# TamagotchiMainBoard.net
KiCad netlist of a schematic drawn in Altium Designer
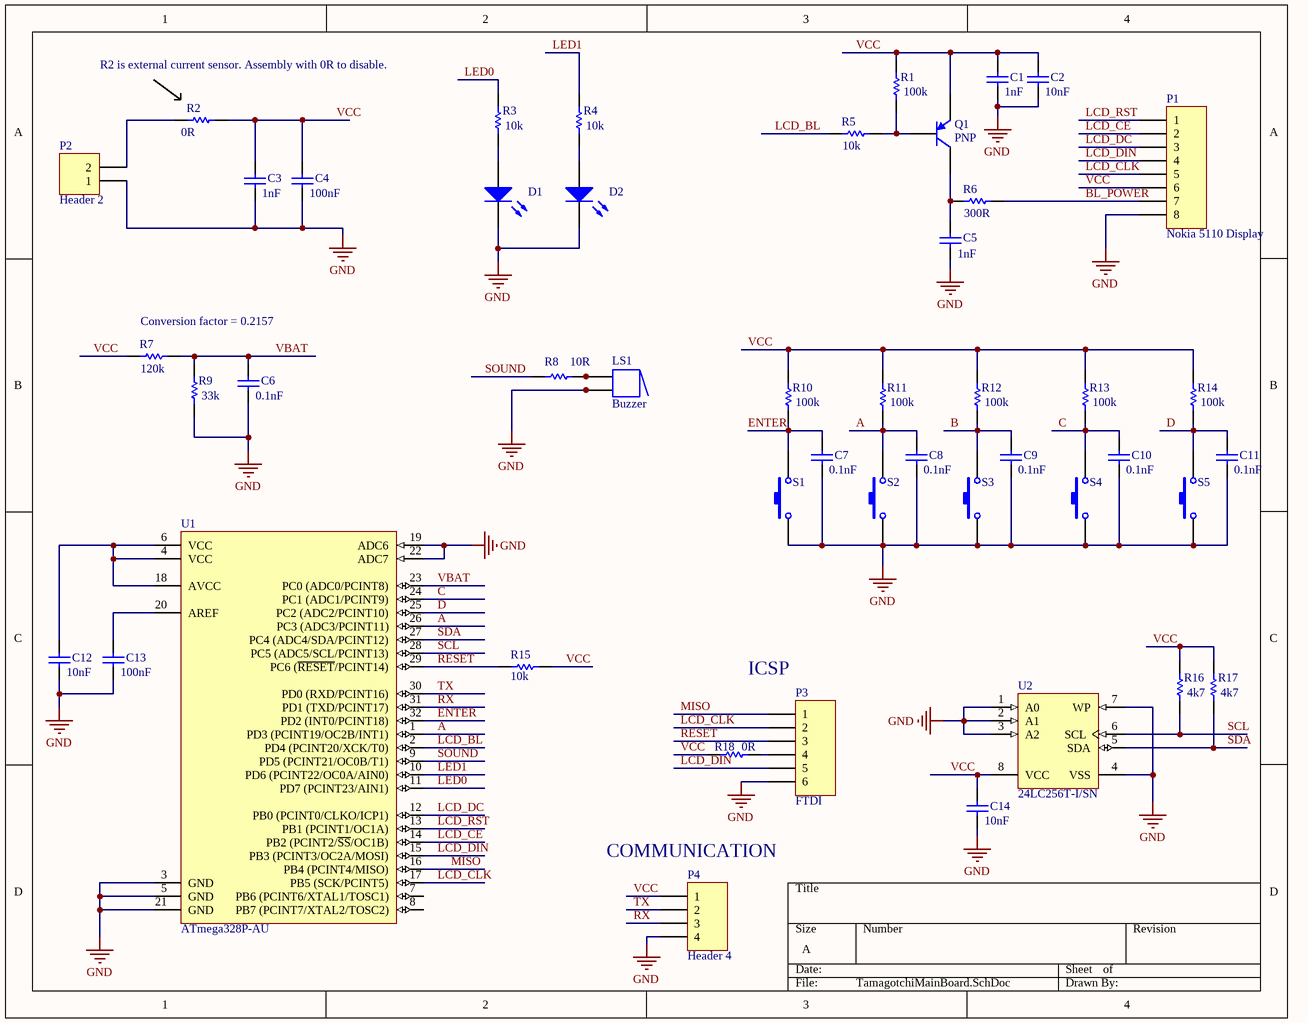
[diagram p0: TamagotchiMainBoard.SchDoc]

(export (version "E")
  (design (tool "Eeschema 10.0.6"))
  (components
    (comp (ref "C1")
      (value "1nF")
      (footprint "Miscellaneous Devices:C0805")
      (description "Capacitor")
      (fields (field (name "Comment") "Cap") (field (name "PUBLISHER") "Altium Limited"))
      (libsource (lib "Miscellaneous Devices") (part "Cap"))
    )
    (comp (ref "C2")
      (value "10nF")
      (footprint "Miscellaneous Devices:C0805")
      (description "Capacitor")
      (fields (field (name "Comment") "Cap") (field (name "PUBLISHER") "Altium Limited"))
      (libsource (lib "Miscellaneous Devices") (part "Cap"))
    )
    (comp (ref "C3")
      (value "1nF")
      (footprint "Miscellaneous Devices:C0805")
      (description "Capacitor")
      (fields (field (name "Comment") "Cap") (field (name "PUBLISHER") "Altium Limited"))
      (libsource (lib "Miscellaneous Devices") (part "Cap"))
    )
    (comp (ref "C4")
      (value "100nF")
      (footprint "Miscellaneous Devices:C0805")
      (description "Capacitor")
      (fields (field (name "Comment") "Cap") (field (name "PUBLISHER") "Altium Limited"))
      (libsource (lib "Miscellaneous Devices") (part "Cap"))
    )
    (comp (ref "C5")
      (value "1nF")
      (footprint "Miscellaneous Devices:C0805")
      (description "Capacitor")
      (fields (field (name "Comment") "Cap") (field (name "PUBLISHER") "Altium Limited"))
      (libsource (lib "Miscellaneous Devices") (part "Cap"))
    )
    (comp (ref "C6")
      (value "0.1nF")
      (footprint "Miscellaneous Devices:C0805")
      (description "Capacitor")
      (fields (field (name "Comment") "Cap") (field (name "PUBLISHER") "Altium Limited"))
      (libsource (lib "Miscellaneous Devices") (part "Cap"))
    )
    (comp (ref "C7")
      (value "0.1nF")
      (footprint "Miscellaneous Devices:C0805")
      (description "Capacitor")
      (fields (field (name "Comment") "Cap") (field (name "PUBLISHER") "Altium Limited"))
      (libsource (lib "Miscellaneous Devices") (part "Cap"))
    )
    (comp (ref "C8")
      (value "0.1nF")
      (footprint "Miscellaneous Devices:C0805")
      (description "Capacitor")
      (fields (field (name "Comment") "Cap") (field (name "PUBLISHER") "Altium Limited"))
      (libsource (lib "Miscellaneous Devices") (part "Cap"))
    )
    (comp (ref "C9")
      (value "0.1nF")
      (footprint "Miscellaneous Devices:C0805")
      (description "Capacitor")
      (fields (field (name "Comment") "Cap") (field (name "PUBLISHER") "Altium Limited"))
      (libsource (lib "Miscellaneous Devices") (part "Cap"))
    )
    (comp (ref "C10")
      (value "0.1nF")
      (footprint "Miscellaneous Devices:C0805")
      (description "Capacitor")
      (fields (field (name "Comment") "Cap") (field (name "PUBLISHER") "Altium Limited"))
      (libsource (lib "Miscellaneous Devices") (part "Cap"))
    )
    (comp (ref "C11")
      (value "0.1nF")
      (footprint "Miscellaneous Devices:C0805")
      (description "Capacitor")
      (fields (field (name "Comment") "Cap") (field (name "PUBLISHER") "Altium Limited"))
      (libsource (lib "Miscellaneous Devices") (part "Cap"))
    )
    (comp (ref "C12")
      (value "10nF")
      (footprint "Miscellaneous Devices:C0805")
      (description "Capacitor")
      (fields (field (name "Comment") "Cap") (field (name "PUBLISHER") "Altium Limited"))
      (libsource (lib "Miscellaneous Devices") (part "Cap"))
    )
    (comp (ref "C13")
      (value "100nF")
      (footprint "Miscellaneous Devices:C0805")
      (description "Capacitor")
      (fields (field (name "Comment") "Cap") (field (name "PUBLISHER") "Altium Limited"))
      (libsource (lib "Miscellaneous Devices") (part "Cap"))
    )
    (comp (ref "C14")
      (value "10nF")
      (footprint "Miscellaneous Devices:C0805")
      (description "Capacitor")
      (fields (field (name "Comment") "Cap") (field (name "PUBLISHER") "Altium Limited"))
      (libsource (lib "Miscellaneous Devices") (part "Cap"))
    )
    (comp (ref "D1")
      (value "LED0")
      (description "Typical INFRARED GaAs LED")
      (fields (field (name "PUBLISHER") "Altium Limited"))
      (libsource (lib "Miscellaneous Devices") (part "LED0"))
    )
    (comp (ref "D2")
      (value "LED0")
      (description "Typical INFRARED GaAs LED")
      (fields (field (name "PUBLISHER") "Altium Limited"))
      (libsource (lib "Miscellaneous Devices") (part "LED0"))
    )
    (comp (ref "LS1")
      (value "Buzzer")
      (footprint "ABSM-1574")
      (description "Magnetic Transducer Buzzer")
      (fields (field (name "PUBLISHER") "Altium Limited"))
      (libsource (lib "Miscellaneous Devices") (part "Buzzer"))
    )
    (comp (ref "P1")
      (value "Nokia 5110 Display")
      (footprint "HDR1X8")
      (description "Header, 8-Pin")
      (fields (field (name "PUBLISHER") "Altium Limited"))
      (libsource (lib "Miscellaneous Connectors") (part "Header 8"))
    )
    (comp (ref "P2")
      (value "Header 2")
      (footprint "HDR1X2")
      (description "Header, 2-Pin")
      (fields (field (name "PUBLISHER") "Altium Limited"))
      (libsource (lib "Miscellaneous Connectors") (part "Header 2"))
    )
    (comp (ref "P3")
      (value "FTDI")
      (footprint "HDR1X6")
      (description "Header, 6-Pin")
      (fields (field (name "PUBLISHER") "Altium Limited"))
      (libsource (lib "Miscellaneous Connectors") (part "Header 6"))
    )
    (comp (ref "P4")
      (value "Header 4")
      (footprint "HDR1X4")
      (description "Header, 4-Pin")
      (fields (field (name "PUBLISHER") "Altium Limited"))
      (libsource (lib "Miscellaneous Connectors") (part "Header 4"))
    )
    (comp (ref "Q1")
      (value "PNP")
      (footprint "SOT-23B_N")
      (description "PNP Bipolar Transistor")
      (fields (field (name "PUBLISHER") "Altium Limited"))
      (libsource (lib "Miscellaneous Devices") (part "PNP"))
    )
    (comp (ref "R1")
      (value "100k")
      (footprint "6-0805_M")
      (description "Resistor")
      (fields (field (name "Comment") "Res1") (field (name "PUBLISHER") "Altium Limited"))
      (libsource (lib "Miscellaneous Devices") (part "Res1"))
    )
    (comp (ref "R2")
      (value "0R")
      (footprint "6-0805_M")
      (description "Resistor")
      (fields (field (name "Comment") "Res1") (field (name "PUBLISHER") "Altium Limited"))
      (libsource (lib "Miscellaneous Devices") (part "Res1"))
    )
    (comp (ref "R3")
      (value "10k")
      (footprint "6-0805_M")
      (description "Resistor")
      (fields (field (name "Comment") "Res1") (field (name "PUBLISHER") "Altium Limited"))
      (libsource (lib "Miscellaneous Devices") (part "Res1"))
    )
    (comp (ref "R4")
      (value "10k")
      (footprint "6-0805_M")
      (description "Resistor")
      (fields (field (name "Comment") "Res1") (field (name "PUBLISHER") "Altium Limited"))
      (libsource (lib "Miscellaneous Devices") (part "Res1"))
    )
    (comp (ref "R5")
      (value "10k")
      (footprint "6-0805_M")
      (description "Resistor")
      (fields (field (name "Comment") "Res1") (field (name "PUBLISHER") "Altium Limited"))
      (libsource (lib "Miscellaneous Devices") (part "Res1"))
    )
    (comp (ref "R6")
      (value "300R")
      (footprint "6-0805_M")
      (description "Resistor")
      (fields (field (name "Comment") "Res1") (field (name "PUBLISHER") "Altium Limited"))
      (libsource (lib "Miscellaneous Devices") (part "Res1"))
    )
    (comp (ref "R7")
      (value "120k")
      (footprint "6-0805_M")
      (description "Resistor")
      (fields (field (name "Comment") "Res1") (field (name "PUBLISHER") "Altium Limited"))
      (libsource (lib "Miscellaneous Devices") (part "Res1"))
    )
    (comp (ref "R8")
      (value "10R")
      (footprint "6-0805_M")
      (description "Resistor")
      (fields (field (name "Comment") "Res1") (field (name "PUBLISHER") "Altium Limited"))
      (libsource (lib "Miscellaneous Devices") (part "Res1"))
    )
    (comp (ref "R9")
      (value "33k")
      (footprint "6-0805_M")
      (description "Resistor")
      (fields (field (name "Comment") "Res1") (field (name "PUBLISHER") "Altium Limited"))
      (libsource (lib "Miscellaneous Devices") (part "Res1"))
    )
    (comp (ref "R10")
      (value "100k")
      (footprint "6-0805_M")
      (description "Resistor")
      (fields (field (name "Comment") "Res1") (field (name "PUBLISHER") "Altium Limited"))
      (libsource (lib "Miscellaneous Devices") (part "Res1"))
    )
    (comp (ref "R11")
      (value "100k")
      (footprint "6-0805_M")
      (description "Resistor")
      (fields (field (name "Comment") "Res1") (field (name "PUBLISHER") "Altium Limited"))
      (libsource (lib "Miscellaneous Devices") (part "Res1"))
    )
    (comp (ref "R12")
      (value "100k")
      (footprint "6-0805_M")
      (description "Resistor")
      (fields (field (name "Comment") "Res1") (field (name "PUBLISHER") "Altium Limited"))
      (libsource (lib "Miscellaneous Devices") (part "Res1"))
    )
    (comp (ref "R13")
      (value "100k")
      (footprint "6-0805_M")
      (description "Resistor")
      (fields (field (name "Comment") "Res1") (field (name "PUBLISHER") "Altium Limited"))
      (libsource (lib "Miscellaneous Devices") (part "Res1"))
    )
    (comp (ref "R14")
      (value "100k")
      (footprint "6-0805_M")
      (description "Resistor")
      (fields (field (name "Comment") "Res1") (field (name "PUBLISHER") "Altium Limited"))
      (libsource (lib "Miscellaneous Devices") (part "Res1"))
    )
    (comp (ref "R15")
      (value "10k")
      (footprint "6-0805_M")
      (description "Resistor")
      (fields (field (name "Comment") "Res1") (field (name "PUBLISHER") "Altium Limited"))
      (libsource (lib "Miscellaneous Devices") (part "Res1"))
    )
    (comp (ref "R16")
      (value "4k7")
      (footprint "6-0805_M")
      (description "Resistor")
      (fields (field (name "Comment") "Res1") (field (name "PUBLISHER") "Altium Limited"))
      (libsource (lib "Miscellaneous Devices") (part "Res1"))
    )
    (comp (ref "R17")
      (value "4k7")
      (footprint "6-0805_M")
      (description "Resistor")
      (fields (field (name "Comment") "Res1") (field (name "PUBLISHER") "Altium Limited"))
      (libsource (lib "Miscellaneous Devices") (part "Res1"))
    )
    (comp (ref "R18")
      (value "0R")
      (footprint "6-0805_M")
      (description "Resistor")
      (fields (field (name "Comment") "Res1") (field (name "PUBLISHER") "Altium Limited"))
      (libsource (lib "Miscellaneous Devices") (part "Res1"))
    )
    (comp (ref "S1")
      (value "SW-PB")
      (footprint "SPST-2")
      (description "Switch")
      (fields (field (name "PUBLISHER") "Altium Limited"))
      (libsource (lib "Miscellaneous Devices") (part "SW-PB"))
    )
    (comp (ref "S2")
      (value "SW-PB")
      (footprint "SPST-2")
      (description "Switch")
      (fields (field (name "PUBLISHER") "Altium Limited"))
      (libsource (lib "Miscellaneous Devices") (part "SW-PB"))
    )
    (comp (ref "S3")
      (value "SW-PB")
      (footprint "SPST-2")
      (description "Switch")
      (fields (field (name "PUBLISHER") "Altium Limited"))
      (libsource (lib "Miscellaneous Devices") (part "SW-PB"))
    )
    (comp (ref "S4")
      (value "SW-PB")
      (footprint "SPST-2")
      (description "Switch")
      (fields (field (name "PUBLISHER") "Altium Limited"))
      (libsource (lib "Miscellaneous Devices") (part "SW-PB"))
    )
    (comp (ref "S5")
      (value "SW-PB")
      (footprint "SPST-2")
      (description "Switch")
      (fields (field (name "PUBLISHER") "Altium Limited"))
      (libsource (lib "Miscellaneous Devices") (part "SW-PB"))
    )
    (comp (ref "U1")
      (value "ATmega328P-AU")
      (footprint "32A_N")
      (fields (field (name "PUBLISHER") "Altium Limited"))
      (libsource (lib "Atmel Microcontroller 8-Bit megaAVR") (part "ATmega328P-AU"))
    )
    (comp (ref "U2")
      (value "24LC256T-I/SN")
      (footprint "SOIC-SN8_N")
      (description "256Kbit, 400kHz, 2.5V, I2C Serial EEPROM, 8-Pin SOIC 150mil, Industrial Temperature, Tape and Reel")
      (fields (field (name "PUBLISHER") "Altium Limited"))
      (libsource (lib "Microchip Memory I2C Serial EEPROM") (part "24LC256T-I/SN"))
    )
  )
  (nets
    (net (code "1") (name "/A") (class "Default")
      (node (ref "C8") (pin "1") (pinfunction "1_1") (pintype "passive"))
      (node (ref "R11") (pin "2") (pinfunction "2_2") (pintype "passive"))
      (node (ref "S2") (pin "2") (pinfunction "2_2") (pintype "passive"))
      (node (ref "U1") (pin "1") (pinfunction "PD3_(PCINT19/OC2B/INT1)_1") (pintype "bidirectional"))
      (node (ref "U1") (pin "26") (pinfunction "PC3_(ADC3/PCINT11)_26") (pintype "bidirectional"))
    )
    (net (code "2") (name "/B") (class "Default")
      (node (ref "C9") (pin "1") (pinfunction "1_1") (pintype "passive"))
      (node (ref "R12") (pin "2") (pinfunction "2_2") (pintype "passive"))
      (node (ref "S3") (pin "2") (pinfunction "2_2") (pintype "passive"))
    )
    (net (code "3") (name "/BL_POWER") (class "Default")
      (node (ref "P1") (pin "7") (pinfunction "7_7") (pintype "passive"))
      (node (ref "R6") (pin "1") (pinfunction "1_1") (pintype "passive"))
    )
    (net (code "4") (name "/C") (class "Default")
      (node (ref "C10") (pin "1") (pinfunction "1_1") (pintype "passive"))
      (node (ref "R13") (pin "2") (pinfunction "2_2") (pintype "passive"))
      (node (ref "S4") (pin "2") (pinfunction "2_2") (pintype "passive"))
      (node (ref "U1") (pin "24") (pinfunction "PC1_(ADC1/PCINT9)_24") (pintype "bidirectional"))
    )
    (net (code "5") (name "/D") (class "Default")
      (node (ref "C11") (pin "1") (pinfunction "1_1") (pintype "passive"))
      (node (ref "R14") (pin "2") (pinfunction "2_2") (pintype "passive"))
      (node (ref "S5") (pin "2") (pinfunction "2_2") (pintype "passive"))
      (node (ref "U1") (pin "25") (pinfunction "PC2_(ADC2/PCINT10)_25") (pintype "bidirectional"))
    )
    (net (code "6") (name "/ENTER") (class "Default")
      (node (ref "C7") (pin "1") (pinfunction "1_1") (pintype "passive"))
      (node (ref "R10") (pin "2") (pinfunction "2_2") (pintype "passive"))
      (node (ref "S1") (pin "2") (pinfunction "2_2") (pintype "passive"))
      (node (ref "U1") (pin "32") (pinfunction "PD2_(INT0/PCINT18)_32") (pintype "bidirectional"))
    )
    (net (code "7") (name "/LCD_BL") (class "Default")
      (node (ref "R5") (pin "2") (pinfunction "2_2") (pintype "passive"))
      (node (ref "U1") (pin "2") (pinfunction "PD4_(PCINT20/XCK/T0)_2") (pintype "bidirectional"))
    )
    (net (code "8") (name "/LCD_CE") (class "Default")
      (node (ref "P1") (pin "2") (pinfunction "2_2") (pintype "passive"))
      (node (ref "U1") (pin "14") (pinfunction "PB2_(PCINT2/~{SS}/OC1B)_14") (pintype "bidirectional"))
    )
    (net (code "9") (name "/LCD_CLK") (class "Default")
      (node (ref "P1") (pin "5") (pinfunction "5_5") (pintype "passive"))
      (node (ref "P3") (pin "2") (pinfunction "2_2") (pintype "passive"))
      (node (ref "U1") (pin "17") (pinfunction "PB5_(SCK/PCINT5)_17") (pintype "bidirectional"))
    )
    (net (code "10") (name "/LCD_DC") (class "Default")
      (node (ref "P1") (pin "3") (pinfunction "3_3") (pintype "passive"))
      (node (ref "U1") (pin "12") (pinfunction "PB0_(PCINT0/CLKO/ICP1)_12") (pintype "bidirectional"))
    )
    (net (code "11") (name "/LCD_DIN") (class "Default")
      (node (ref "P1") (pin "4") (pinfunction "4_4") (pintype "passive"))
      (node (ref "P3") (pin "5") (pinfunction "5_5") (pintype "passive"))
      (node (ref "U1") (pin "15") (pinfunction "PB3_(PCINT3/OC2A/MOSI)_15") (pintype "bidirectional"))
    )
    (net (code "12") (name "/LCD_RST") (class "Default")
      (node (ref "P1") (pin "1") (pinfunction "1_1") (pintype "passive"))
      (node (ref "U1") (pin "13") (pinfunction "PB1_(PCINT1/OC1A)_13") (pintype "bidirectional"))
    )
    (net (code "13") (name "/LED0") (class "Default")
      (node (ref "R3") (pin "1") (pinfunction "1_1") (pintype "passive"))
      (node (ref "U1") (pin "11") (pinfunction "PD7_(PCINT23/AIN1)_11") (pintype "bidirectional"))
    )
    (net (code "14") (name "/LED1") (class "Default")
      (node (ref "R4") (pin "1") (pinfunction "1_1") (pintype "passive"))
      (node (ref "U1") (pin "10") (pinfunction "PD6_(PCINT22/OC0A/AIN0)_10") (pintype "bidirectional"))
    )
    (net (code "15") (name "/MISO") (class "Default")
      (node (ref "P3") (pin "1") (pinfunction "1_1") (pintype "passive"))
      (node (ref "U1") (pin "16") (pinfunction "PB4_(PCINT4/MISO)_16") (pintype "bidirectional"))
    )
    (net (code "16") (name "/RESET") (class "Default")
      (node (ref "P3") (pin "3") (pinfunction "3_3") (pintype "passive"))
      (node (ref "R15") (pin "1") (pinfunction "1_1") (pintype "passive"))
      (node (ref "U1") (pin "29") (pinfunction "PC6_(~{RESET}/PCINT14)_29") (pintype "bidirectional"))
    )
    (net (code "17") (name "/RX") (class "Default")
      (node (ref "P4") (pin "3") (pinfunction "3_3") (pintype "passive"))
      (node (ref "U1") (pin "31") (pinfunction "PD1_(TXD/PCINT17)_31") (pintype "bidirectional"))
    )
    (net (code "18") (name "/SCL") (class "Default")
      (node (ref "R16") (pin "2") (pinfunction "2_2") (pintype "passive"))
      (node (ref "U1") (pin "28") (pinfunction "PC5_(ADC5/SCL/PCINT13)_28") (pintype "bidirectional"))
      (node (ref "U2") (pin "6") (pinfunction "SCL_6") (pintype "input"))
    )
    (net (code "19") (name "/SDA") (class "Default")
      (node (ref "R17") (pin "2") (pinfunction "2_2") (pintype "passive"))
      (node (ref "U1") (pin "27") (pinfunction "PC4_(ADC4/SDA/PCINT12)_27") (pintype "bidirectional"))
      (node (ref "U2") (pin "5") (pinfunction "SDA_5") (pintype "bidirectional"))
    )
    (net (code "20") (name "/SOUND") (class "Default")
      (node (ref "R8") (pin "1") (pinfunction "1_1") (pintype "passive"))
      (node (ref "U1") (pin "9") (pinfunction "PD5_(PCINT21/OC0B/T1)_9") (pintype "bidirectional"))
    )
    (net (code "21") (name "/TX") (class "Default")
      (node (ref "P4") (pin "2") (pinfunction "2_2") (pintype "passive"))
      (node (ref "U1") (pin "30") (pinfunction "PD0_(RXD/PCINT16)_30") (pintype "bidirectional"))
    )
    (net (code "22") (name "/VBAT") (class "Default")
      (node (ref "C6") (pin "1") (pinfunction "1_1") (pintype "passive"))
      (node (ref "R7") (pin "1") (pinfunction "1_1") (pintype "passive"))
      (node (ref "R9") (pin "1") (pinfunction "1_1") (pintype "passive"))
      (node (ref "U1") (pin "23") (pinfunction "PC0_(ADC0/PCINT8)_23") (pintype "bidirectional"))
    )
    (net (code "23") (name "/VCC") (class "Default")
      (node (ref "C1") (pin "2") (pinfunction "2_2") (pintype "passive"))
      (node (ref "C14") (pin "2") (pinfunction "2_2") (pintype "passive"))
      (node (ref "C2") (pin "2") (pinfunction "2_2") (pintype "passive"))
      (node (ref "C3") (pin "2") (pinfunction "2_2") (pintype "passive"))
      (node (ref "C4") (pin "2") (pinfunction "2_2") (pintype "passive"))
      (node (ref "P1") (pin "6") (pinfunction "6_6") (pintype "passive"))
      (node (ref "P4") (pin "1") (pinfunction "1_1") (pintype "passive"))
      (node (ref "Q1") (pin "3") (pinfunction "E_3") (pintype "passive"))
      (node (ref "R1") (pin "1") (pinfunction "1_1") (pintype "passive"))
      (node (ref "R10") (pin "1") (pinfunction "1_1") (pintype "passive"))
      (node (ref "R11") (pin "1") (pinfunction "1_1") (pintype "passive"))
      (node (ref "R12") (pin "1") (pinfunction "1_1") (pintype "passive"))
      (node (ref "R13") (pin "1") (pinfunction "1_1") (pintype "passive"))
      (node (ref "R14") (pin "1") (pinfunction "1_1") (pintype "passive"))
      (node (ref "R15") (pin "2") (pinfunction "2_2") (pintype "passive"))
      (node (ref "R16") (pin "1") (pinfunction "1_1") (pintype "passive"))
      (node (ref "R17") (pin "1") (pinfunction "1_1") (pintype "passive"))
      (node (ref "R18") (pin "1") (pinfunction "1_1") (pintype "passive"))
      (node (ref "R2") (pin "1") (pinfunction "1_1") (pintype "passive"))
      (node (ref "R7") (pin "2") (pinfunction "2_2") (pintype "passive"))
      (node (ref "U2") (pin "8") (pinfunction "VCC_8") (pintype "power_in"))
    )
    (net (code "24") (name "GND") (class "Default")
      (node (ref "C1") (pin "1") (pinfunction "1_1") (pintype "passive"))
      (node (ref "C10") (pin "2") (pinfunction "2_2") (pintype "passive"))
      (node (ref "C11") (pin "2") (pinfunction "2_2") (pintype "passive"))
      (node (ref "C12") (pin "1") (pinfunction "1_1") (pintype "passive"))
      (node (ref "C13") (pin "1") (pinfunction "1_1") (pintype "passive"))
      (node (ref "C14") (pin "1") (pinfunction "1_1") (pintype "passive"))
      (node (ref "C2") (pin "1") (pinfunction "1_1") (pintype "passive"))
      (node (ref "C3") (pin "1") (pinfunction "1_1") (pintype "passive"))
      (node (ref "C4") (pin "1") (pinfunction "1_1") (pintype "passive"))
      (node (ref "C5") (pin "1") (pinfunction "1_1") (pintype "passive"))
      (node (ref "C6") (pin "2") (pinfunction "2_2") (pintype "passive"))
      (node (ref "C7") (pin "2") (pinfunction "2_2") (pintype "passive"))
      (node (ref "C8") (pin "2") (pinfunction "2_2") (pintype "passive"))
      (node (ref "C9") (pin "2") (pinfunction "2_2") (pintype "passive"))
      (node (ref "D1") (pin "2") (pinfunction "K_2") (pintype "passive"))
      (node (ref "D2") (pin "2") (pinfunction "K_2") (pintype "passive"))
      (node (ref "LS1") (pin "2") (pinfunction "2_2") (pintype "passive"))
      (node (ref "LS1") (pin "2A") (pinfunction "2A_2A") (pintype "passive"))
      (node (ref "P1") (pin "8") (pinfunction "8_8") (pintype "passive"))
      (node (ref "P2") (pin "1") (pinfunction "1_1") (pintype "passive"))
      (node (ref "P3") (pin "6") (pinfunction "6_6") (pintype "passive"))
      (node (ref "P4") (pin "4") (pinfunction "4_4") (pintype "passive"))
      (node (ref "R9") (pin "2") (pinfunction "2_2") (pintype "passive"))
      (node (ref "S1") (pin "1") (pinfunction "1_1") (pintype "passive"))
      (node (ref "S2") (pin "1") (pinfunction "1_1") (pintype "passive"))
      (node (ref "S3") (pin "1") (pinfunction "1_1") (pintype "passive"))
      (node (ref "S4") (pin "1") (pinfunction "1_1") (pintype "passive"))
      (node (ref "S5") (pin "1") (pinfunction "1_1") (pintype "passive"))
      (node (ref "U1") (pin "19") (pinfunction "ADC6_19") (pintype "input"))
      (node (ref "U1") (pin "21") (pinfunction "GND_21") (pintype "power_in"))
      (node (ref "U1") (pin "22") (pinfunction "ADC7_22") (pintype "input"))
      (node (ref "U1") (pin "3") (pinfunction "GND_3") (pintype "power_in"))
      (node (ref "U1") (pin "5") (pinfunction "GND_5") (pintype "power_in"))
      (node (ref "U2") (pin "1") (pinfunction "A0_1") (pintype "input"))
      (node (ref "U2") (pin "2") (pinfunction "A1_2") (pintype "input"))
      (node (ref "U2") (pin "3") (pinfunction "A2_3") (pintype "input"))
      (node (ref "U2") (pin "4") (pinfunction "VSS_4") (pintype "power_in"))
      (node (ref "U2") (pin "7") (pinfunction "WP_7") (pintype "input"))
    )
    (net (code "25") (name "Net-(D1-A)") (class "Default")
      (node (ref "D1") (pin "1") (pinfunction "A_1") (pintype "passive"))
      (node (ref "R3") (pin "2") (pinfunction "2_2") (pintype "passive"))
    )
    (net (code "26") (name "Net-(D2-A)") (class "Default")
      (node (ref "D2") (pin "1") (pinfunction "A_1") (pintype "passive"))
      (node (ref "R4") (pin "2") (pinfunction "2_2") (pintype "passive"))
    )
    (net (code "27") (name "Net-(LS1-Pad1)") (class "Default")
      (node (ref "LS1") (pin "1") (pinfunction "1_1") (pintype "passive"))
      (node (ref "LS1") (pin "1A") (pinfunction "1A_1A") (pintype "passive"))
      (node (ref "R8") (pin "2") (pinfunction "2_2") (pintype "passive"))
    )
    (net (code "28") (name "Net-(P2-Pad2)") (class "Default")
      (node (ref "P2") (pin "2") (pinfunction "2_2") (pintype "passive"))
      (node (ref "R2") (pin "2") (pinfunction "2_2") (pintype "passive"))
    )
    (net (code "29") (name "Net-(P3-Pad4)") (class "Default")
      (node (ref "P3") (pin "4") (pinfunction "4_4") (pintype "passive"))
      (node (ref "R18") (pin "2") (pinfunction "2_2") (pintype "passive"))
    )
    (net (code "30") (name "Net-(Q1-B)") (class "Default")
      (node (ref "Q1") (pin "2") (pinfunction "B_2") (pintype "passive"))
      (node (ref "R1") (pin "2") (pinfunction "2_2") (pintype "passive"))
      (node (ref "R5") (pin "1") (pinfunction "1_1") (pintype "passive"))
    )
    (net (code "31") (name "Net-(Q1-C)") (class "Default")
      (node (ref "C5") (pin "2") (pinfunction "2_2") (pintype "passive"))
      (node (ref "Q1") (pin "1") (pinfunction "C_1") (pintype "passive"))
      (node (ref "R6") (pin "2") (pinfunction "2_2") (pintype "passive"))
    )
    (net (code "32") (name "Net-(U1-AREF)") (class "Default")
      (node (ref "C13") (pin "2") (pinfunction "2_2") (pintype "passive"))
      (node (ref "U1") (pin "20") (pinfunction "AREF_20") (pintype "passive"))
    )
    (net (code "33") (name "Net-(U1-AVCC)") (class "Default")
      (node (ref "C12") (pin "2") (pinfunction "2_2") (pintype "passive"))
      (node (ref "U1") (pin "18") (pinfunction "AVCC_18") (pintype "power_in"))
      (node (ref "U1") (pin "4") (pinfunction "VCC_4") (pintype "power_in"))
      (node (ref "U1") (pin "6") (pinfunction "VCC_6") (pintype "power_in"))
    )
    (net (code "34") (name "unconnected-(U1-PB6_(PCINT6{slash}XTAL1{slash}TOSC1)-Pad7)") (class "Default")
      (node (ref "U1") (pin "7") (pinfunction "PB6_(PCINT6/XTAL1/TOSC1)_7") (pintype "bidirectional"))
    )
    (net (code "35") (name "unconnected-(U1-PB7_(PCINT7{slash}XTAL2{slash}TOSC2)-Pad8)") (class "Default")
      (node (ref "U1") (pin "8") (pinfunction "PB7_(PCINT7/XTAL2/TOSC2)_8") (pintype "bidirectional"))
    )
  )
)
